# CCP_MCU_IO_CN11.net
KiCad netlist of a schematic drawn in Altium Designer
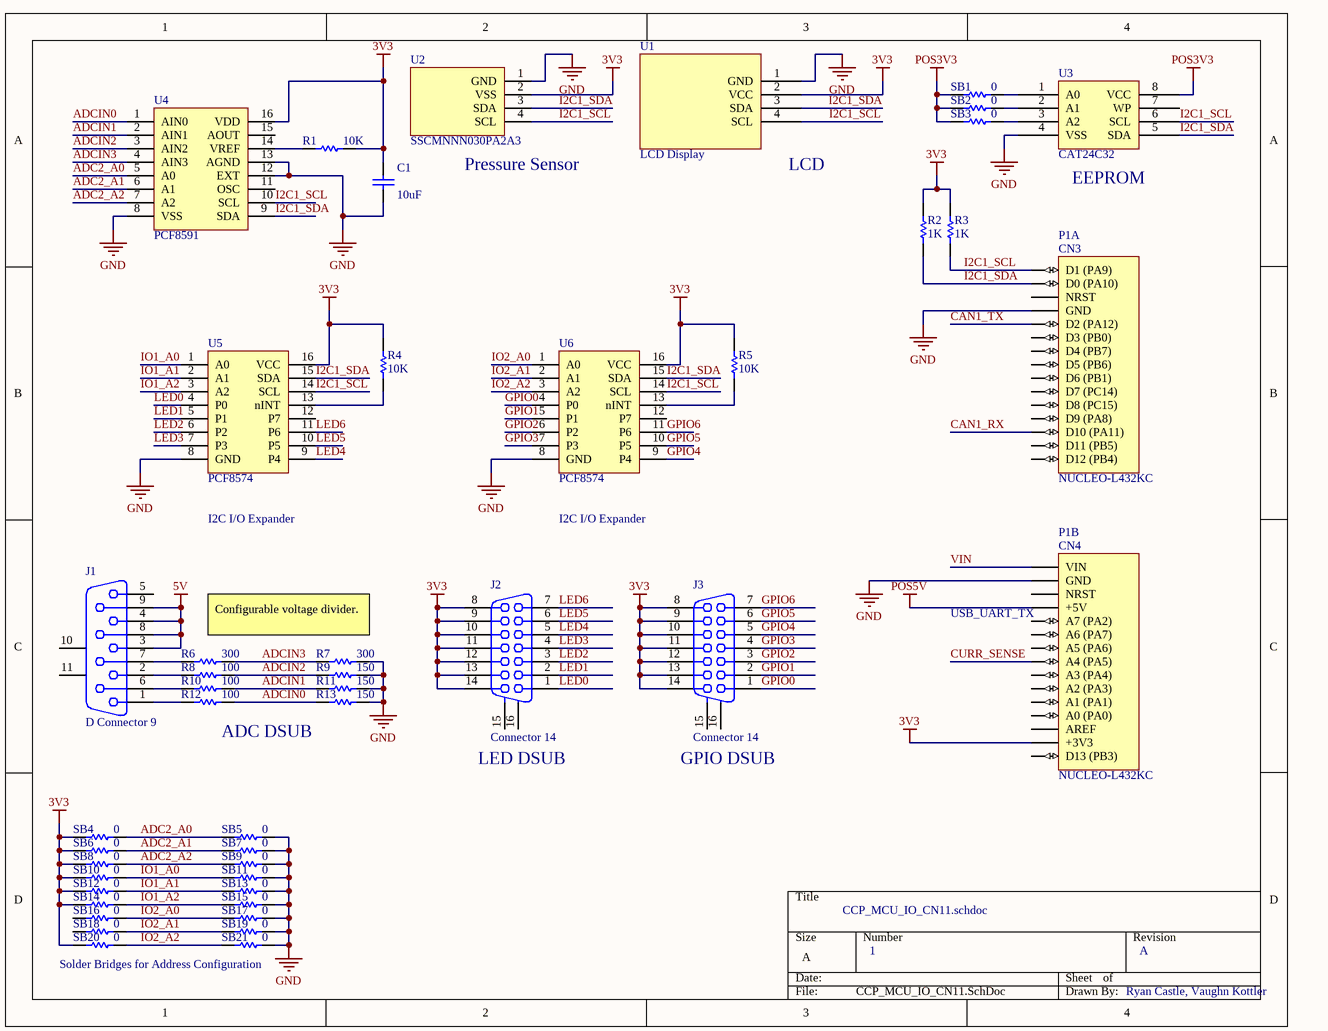
[diagram p0: CCP_MCU_IO_CN11.SchDoc]

(export (version "E")
  (design (tool "Eeschema 10.0.6"))
  (components
    (comp (ref "C1")
      (value "10uF")
      (footprint "C1206")
      (description "Capacitor")
      (fields (field (name "Comment") "Cap") (field (name "PUBLISHER") "Altium Limited"))
      (libsource (lib "Miscellaneous Devices") (part "Cap"))
    )
    (comp (ref "J1")
      (value "D Connector 9")
      (footprint "DSUB1.385-2H9")
      (description "Receptacle Assembly, 9 Position, Right Angle")
      (fields (field (name "PUBLISHER") "Altium Limited"))
      (libsource (lib "Miscellaneous Connectors") (part "D Connector 9"))
    )
    (comp (ref "J2")
      (value "Connector 14")
      (footprint "CHAMP1.27-2H14A")
      (description "Receptacle Header Assemby")
      (fields (field (name "PUBLISHER") "Altium Limited"))
      (libsource (lib "Miscellaneous Connectors") (part "Connector 14"))
    )
    (comp (ref "J3")
      (value "Connector 14")
      (footprint "CHAMP1.27-2H14A")
      (description "Receptacle Header Assemby")
      (fields (field (name "PUBLISHER") "Altium Limited"))
      (libsource (lib "Miscellaneous Connectors") (part "Connector 14"))
    )
    (comp (ref "P1")
      (value "NUCLEO-L432KC")
      (footprint "NUCLEO-32")
      (description "STM32L432KC Development Board")
      (libsource (lib "ic") (part "NUCLEO-L432KC"))
    )
    (comp (ref "R1")
      (value "10K")
      (footprint "6-0805_M")
      (description "Resistor")
      (fields (field (name "Comment") "Res1") (field (name "PUBLISHER") "Altium Limited"))
      (libsource (lib "Miscellaneous Devices") (part "Res1"))
    )
    (comp (ref "R2")
      (value "1K")
      (footprint "6-0805_M")
      (description "Resistor")
      (fields (field (name "Comment") "Res1") (field (name "PUBLISHER") "Altium Limited"))
      (libsource (lib "Miscellaneous Devices") (part "Res1"))
    )
    (comp (ref "R3")
      (value "1K")
      (footprint "6-0805_M")
      (description "Resistor")
      (fields (field (name "Comment") "Res1") (field (name "PUBLISHER") "Altium Limited"))
      (libsource (lib "Miscellaneous Devices") (part "Res1"))
    )
    (comp (ref "R4")
      (value "10K")
      (footprint "6-0805_M")
      (description "Resistor")
      (fields (field (name "Comment") "Res1") (field (name "PUBLISHER") "Altium Limited"))
      (libsource (lib "Miscellaneous Devices") (part "Res1"))
    )
    (comp (ref "R5")
      (value "10K")
      (footprint "6-0805_M")
      (description "Resistor")
      (fields (field (name "Comment") "Res1") (field (name "PUBLISHER") "Altium Limited"))
      (libsource (lib "Miscellaneous Devices") (part "Res1"))
    )
    (comp (ref "R6")
      (value "300")
      (footprint "6-0805_M")
      (description "Resistor")
      (fields (field (name "Comment") "Res1") (field (name "PUBLISHER") "Altium Limited"))
      (libsource (lib "Miscellaneous Devices") (part "Res1"))
    )
    (comp (ref "R7")
      (value "300")
      (footprint "6-0805_M")
      (description "Resistor")
      (fields (field (name "Comment") "Res1") (field (name "PUBLISHER") "Altium Limited"))
      (libsource (lib "Miscellaneous Devices") (part "Res1"))
    )
    (comp (ref "R8")
      (value "100")
      (footprint "6-0805_M")
      (description "Resistor")
      (fields (field (name "Comment") "Res1") (field (name "PUBLISHER") "Altium Limited"))
      (libsource (lib "Miscellaneous Devices") (part "Res1"))
    )
    (comp (ref "R9")
      (value "150")
      (footprint "6-0805_M")
      (description "Resistor")
      (fields (field (name "Comment") "Res1") (field (name "PUBLISHER") "Altium Limited"))
      (libsource (lib "Miscellaneous Devices") (part "Res1"))
    )
    (comp (ref "R10")
      (value "100")
      (footprint "6-0805_M")
      (description "Resistor")
      (fields (field (name "Comment") "Res1") (field (name "PUBLISHER") "Altium Limited"))
      (libsource (lib "Miscellaneous Devices") (part "Res1"))
    )
    (comp (ref "R11")
      (value "150")
      (footprint "6-0805_M")
      (description "Resistor")
      (fields (field (name "Comment") "Res1") (field (name "PUBLISHER") "Altium Limited"))
      (libsource (lib "Miscellaneous Devices") (part "Res1"))
    )
    (comp (ref "R12")
      (value "100")
      (footprint "6-0805_M")
      (description "Resistor")
      (fields (field (name "Comment") "Res1") (field (name "PUBLISHER") "Altium Limited"))
      (libsource (lib "Miscellaneous Devices") (part "Res1"))
    )
    (comp (ref "R13")
      (value "150")
      (footprint "6-0805_M")
      (description "Resistor")
      (fields (field (name "Comment") "Res1") (field (name "PUBLISHER") "Altium Limited"))
      (libsource (lib "Miscellaneous Devices") (part "Res1"))
    )
    (comp (ref "SB1")
      (value "0")
      (footprint "6-0805_M")
      (description "Resistor")
      (fields (field (name "Comment") "Res1") (field (name "PUBLISHER") "Altium Limited"))
      (libsource (lib "Miscellaneous Devices") (part "Res1"))
    )
    (comp (ref "SB2")
      (value "0")
      (footprint "6-0805_M")
      (description "Resistor")
      (fields (field (name "Comment") "Res1") (field (name "PUBLISHER") "Altium Limited"))
      (libsource (lib "Miscellaneous Devices") (part "Res1"))
    )
    (comp (ref "SB3")
      (value "0")
      (footprint "6-0805_M")
      (description "Resistor")
      (fields (field (name "Comment") "Res1") (field (name "PUBLISHER") "Altium Limited"))
      (libsource (lib "Miscellaneous Devices") (part "Res1"))
    )
    (comp (ref "SB4")
      (value "0")
      (footprint "6-0805_M")
      (description "Resistor")
      (fields (field (name "Comment") "Res1") (field (name "PUBLISHER") "Altium Limited"))
      (libsource (lib "Miscellaneous Devices") (part "Res1"))
    )
    (comp (ref "SB5")
      (value "0")
      (footprint "6-0805_M")
      (description "Resistor")
      (fields (field (name "Comment") "Res1") (field (name "PUBLISHER") "Altium Limited"))
      (libsource (lib "Miscellaneous Devices") (part "Res1"))
    )
    (comp (ref "SB6")
      (value "0")
      (footprint "6-0805_M")
      (description "Resistor")
      (fields (field (name "Comment") "Res1") (field (name "PUBLISHER") "Altium Limited"))
      (libsource (lib "Miscellaneous Devices") (part "Res1"))
    )
    (comp (ref "SB7")
      (value "0")
      (footprint "6-0805_M")
      (description "Resistor")
      (fields (field (name "Comment") "Res1") (field (name "PUBLISHER") "Altium Limited"))
      (libsource (lib "Miscellaneous Devices") (part "Res1"))
    )
    (comp (ref "SB8")
      (value "0")
      (footprint "6-0805_M")
      (description "Resistor")
      (fields (field (name "Comment") "Res1") (field (name "PUBLISHER") "Altium Limited"))
      (libsource (lib "Miscellaneous Devices") (part "Res1"))
    )
    (comp (ref "SB9")
      (value "0")
      (footprint "6-0805_M")
      (description "Resistor")
      (fields (field (name "Comment") "Res1") (field (name "PUBLISHER") "Altium Limited"))
      (libsource (lib "Miscellaneous Devices") (part "Res1"))
    )
    (comp (ref "SB10")
      (value "0")
      (footprint "6-0805_M")
      (description "Resistor")
      (fields (field (name "Comment") "Res1") (field (name "PUBLISHER") "Altium Limited"))
      (libsource (lib "Miscellaneous Devices") (part "Res1"))
    )
    (comp (ref "SB11")
      (value "0")
      (footprint "6-0805_M")
      (description "Resistor")
      (fields (field (name "Comment") "Res1") (field (name "PUBLISHER") "Altium Limited"))
      (libsource (lib "Miscellaneous Devices") (part "Res1"))
    )
    (comp (ref "SB12")
      (value "0")
      (footprint "6-0805_M")
      (description "Resistor")
      (fields (field (name "Comment") "Res1") (field (name "PUBLISHER") "Altium Limited"))
      (libsource (lib "Miscellaneous Devices") (part "Res1"))
    )
    (comp (ref "SB13")
      (value "0")
      (footprint "6-0805_M")
      (description "Resistor")
      (fields (field (name "Comment") "Res1") (field (name "PUBLISHER") "Altium Limited"))
      (libsource (lib "Miscellaneous Devices") (part "Res1"))
    )
    (comp (ref "SB14")
      (value "0")
      (footprint "6-0805_M")
      (description "Resistor")
      (fields (field (name "Comment") "Res1") (field (name "PUBLISHER") "Altium Limited"))
      (libsource (lib "Miscellaneous Devices") (part "Res1"))
    )
    (comp (ref "SB15")
      (value "0")
      (footprint "6-0805_M")
      (description "Resistor")
      (fields (field (name "Comment") "Res1") (field (name "PUBLISHER") "Altium Limited"))
      (libsource (lib "Miscellaneous Devices") (part "Res1"))
    )
    (comp (ref "SB16")
      (value "0")
      (footprint "6-0805_M")
      (description "Resistor")
      (fields (field (name "Comment") "Res1") (field (name "PUBLISHER") "Altium Limited"))
      (libsource (lib "Miscellaneous Devices") (part "Res1"))
    )
    (comp (ref "SB17")
      (value "0")
      (footprint "6-0805_M")
      (description "Resistor")
      (fields (field (name "Comment") "Res1") (field (name "PUBLISHER") "Altium Limited"))
      (libsource (lib "Miscellaneous Devices") (part "Res1"))
    )
    (comp (ref "SB18")
      (value "0")
      (footprint "6-0805_M")
      (description "Resistor")
      (fields (field (name "Comment") "Res1") (field (name "PUBLISHER") "Altium Limited"))
      (libsource (lib "Miscellaneous Devices") (part "Res1"))
    )
    (comp (ref "SB19")
      (value "0")
      (footprint "6-0805_M")
      (description "Resistor")
      (fields (field (name "Comment") "Res1") (field (name "PUBLISHER") "Altium Limited"))
      (libsource (lib "Miscellaneous Devices") (part "Res1"))
    )
    (comp (ref "SB20")
      (value "0")
      (footprint "6-0805_M")
      (description "Resistor")
      (fields (field (name "Comment") "Res1") (field (name "PUBLISHER") "Altium Limited"))
      (libsource (lib "Miscellaneous Devices") (part "Res1"))
    )
    (comp (ref "SB21")
      (value "0")
      (footprint "6-0805_M")
      (description "Resistor")
      (fields (field (name "Comment") "Res1") (field (name "PUBLISHER") "Altium Limited"))
      (libsource (lib "Miscellaneous Devices") (part "Res1"))
    )
    (comp (ref "U1")
      (value "LCD Display")
      (footprint "4POS TERM BLOCK")
      (libsource (lib "ic") (part "B01LC8HZ2O"))
    )
    (comp (ref "U2")
      (value "SSCMNNN030PA2A3")
      (footprint "8-SMT")
      (description "Honeywell Digital Pressure Sensor")
      (libsource (lib "ic") (part "SSCMNNN030PA2A3"))
    )
    (comp (ref "U3")
      (value "CAT24C32")
      (footprint "SO8_N")
      (description "I2C EEPROM")
      (libsource (lib "ic") (part "CAT24C32"))
    )
    (comp (ref "U4")
      (value "PCF8591")
      (footprint "16-SOIC")
      (description "8-bit A/D and D/A")
      (libsource (lib "ic") (part "PCF8591"))
    )
    (comp (ref "U5")
      (value "PCF8574")
      (footprint "16-SOIC")
      (description "I2C I/O Expander")
      (libsource (lib "ic") (part "PCF8574"))
    )
    (comp (ref "U6")
      (value "PCF8574")
      (footprint "16-SOIC")
      (description "I2C I/O Expander")
      (libsource (lib "ic") (part "PCF8574"))
    )
  )
  (nets
    (net (code "1") (name "/ADC2_A0") (class "Default")
      (node (ref "SB4") (pin "1") (pinfunction "1_1") (pintype "passive"))
      (node (ref "SB5") (pin "2") (pinfunction "2_2") (pintype "passive"))
      (node (ref "U4") (pin "5") (pinfunction "A0_5") (pintype "passive"))
    )
    (net (code "2") (name "/ADC2_A1") (class "Default")
      (node (ref "SB6") (pin "1") (pinfunction "1_1") (pintype "passive"))
      (node (ref "SB7") (pin "2") (pinfunction "2_2") (pintype "passive"))
      (node (ref "U4") (pin "6") (pinfunction "A1_6") (pintype "passive"))
    )
    (net (code "3") (name "/ADC2_A2") (class "Default")
      (node (ref "SB8") (pin "1") (pinfunction "1_1") (pintype "passive"))
      (node (ref "SB9") (pin "2") (pinfunction "2_2") (pintype "passive"))
      (node (ref "U4") (pin "7") (pinfunction "A2_7") (pintype "passive"))
    )
    (net (code "4") (name "/ADCIN0") (class "Default")
      (node (ref "R12") (pin "1") (pinfunction "1_1") (pintype "passive"))
      (node (ref "R13") (pin "2") (pinfunction "2_2") (pintype "passive"))
      (node (ref "U4") (pin "1") (pinfunction "AIN0_1") (pintype "passive"))
    )
    (net (code "5") (name "/ADCIN1") (class "Default")
      (node (ref "R10") (pin "1") (pinfunction "1_1") (pintype "passive"))
      (node (ref "R11") (pin "2") (pinfunction "2_2") (pintype "passive"))
      (node (ref "U4") (pin "2") (pinfunction "AIN1_2") (pintype "passive"))
    )
    (net (code "6") (name "/ADCIN2") (class "Default")
      (node (ref "R8") (pin "1") (pinfunction "1_1") (pintype "passive"))
      (node (ref "R9") (pin "2") (pinfunction "2_2") (pintype "passive"))
      (node (ref "U4") (pin "3") (pinfunction "AIN2_3") (pintype "passive"))
    )
    (net (code "7") (name "/ADCIN3") (class "Default")
      (node (ref "R6") (pin "1") (pinfunction "1_1") (pintype "passive"))
      (node (ref "R7") (pin "2") (pinfunction "2_2") (pintype "passive"))
      (node (ref "U4") (pin "4") (pinfunction "AIN3_4") (pintype "passive"))
    )
    (net (code "8") (name "/CAN1_RX") (class "Default")
      (node (ref "P1") (pin "13") (pinfunction "D10_(PA11)_13") (pintype "bidirectional"))
    )
    (net (code "9") (name "/CAN1_TX") (class "Default")
      (node (ref "P1") (pin "5") (pinfunction "D2_(PA12)_5") (pintype "bidirectional"))
    )
    (net (code "10") (name "/CURR_SENSE") (class "Default")
      (node (ref "P1") (pin "23") (pinfunction "A4_(PA5)_23") (pintype "bidirectional"))
    )
    (net (code "11") (name "/GPIO0") (class "Default")
      (node (ref "J3") (pin "1") (pinfunction "1_1") (pintype "passive"))
      (node (ref "U6") (pin "4") (pinfunction "P0_4") (pintype "passive"))
    )
    (net (code "12") (name "/GPIO1") (class "Default")
      (node (ref "J3") (pin "2") (pinfunction "2_2") (pintype "passive"))
      (node (ref "U6") (pin "5") (pinfunction "P1_5") (pintype "passive"))
    )
    (net (code "13") (name "/GPIO2") (class "Default")
      (node (ref "J3") (pin "3") (pinfunction "3_3") (pintype "passive"))
      (node (ref "U6") (pin "6") (pinfunction "P2_6") (pintype "passive"))
    )
    (net (code "14") (name "/GPIO3") (class "Default")
      (node (ref "J3") (pin "4") (pinfunction "4_4") (pintype "passive"))
      (node (ref "U6") (pin "7") (pinfunction "P3_7") (pintype "passive"))
    )
    (net (code "15") (name "/GPIO4") (class "Default")
      (node (ref "J3") (pin "5") (pinfunction "5_5") (pintype "passive"))
      (node (ref "U6") (pin "9") (pinfunction "P4_9") (pintype "passive"))
    )
    (net (code "16") (name "/GPIO5") (class "Default")
      (node (ref "J3") (pin "6") (pinfunction "6_6") (pintype "passive"))
      (node (ref "U6") (pin "10") (pinfunction "P5_10") (pintype "passive"))
    )
    (net (code "17") (name "/GPIO6") (class "Default")
      (node (ref "J3") (pin "7") (pinfunction "7_7") (pintype "passive"))
      (node (ref "U6") (pin "11") (pinfunction "P6_11") (pintype "passive"))
    )
    (net (code "18") (name "/I2C1_SCL") (class "Default")
      (node (ref "P1") (pin "1") (pinfunction "D1_(PA9)_1") (pintype "bidirectional"))
      (node (ref "R3") (pin "1") (pinfunction "1_1") (pintype "passive"))
      (node (ref "U1") (pin "4") (pinfunction "SCL_4") (pintype "passive"))
      (node (ref "U2") (pin "4") (pinfunction "SCL_4") (pintype "passive"))
      (node (ref "U3") (pin "6") (pinfunction "SCL_6") (pintype "passive"))
      (node (ref "U4") (pin "10") (pinfunction "SCL_10") (pintype "passive"))
      (node (ref "U5") (pin "14") (pinfunction "SCL_14") (pintype "passive"))
      (node (ref "U6") (pin "14") (pinfunction "SCL_14") (pintype "passive"))
    )
    (net (code "19") (name "/I2C1_SDA") (class "Default")
      (node (ref "P1") (pin "2") (pinfunction "D0_(PA10)_2") (pintype "bidirectional"))
      (node (ref "R2") (pin "1") (pinfunction "1_1") (pintype "passive"))
      (node (ref "U1") (pin "3") (pinfunction "SDA_3") (pintype "passive"))
      (node (ref "U2") (pin "3") (pinfunction "SDA_3") (pintype "passive"))
      (node (ref "U3") (pin "5") (pinfunction "SDA_5") (pintype "passive"))
      (node (ref "U4") (pin "9") (pinfunction "SDA_9") (pintype "passive"))
      (node (ref "U5") (pin "15") (pinfunction "SDA_15") (pintype "passive"))
      (node (ref "U6") (pin "15") (pinfunction "SDA_15") (pintype "passive"))
    )
    (net (code "20") (name "/IO1_A0") (class "Default")
      (node (ref "SB10") (pin "1") (pinfunction "1_1") (pintype "passive"))
      (node (ref "SB11") (pin "2") (pinfunction "2_2") (pintype "passive"))
      (node (ref "U5") (pin "1") (pinfunction "A0_1") (pintype "passive"))
    )
    (net (code "21") (name "/IO1_A1") (class "Default")
      (node (ref "SB12") (pin "1") (pinfunction "1_1") (pintype "passive"))
      (node (ref "SB13") (pin "2") (pinfunction "2_2") (pintype "passive"))
      (node (ref "U5") (pin "2") (pinfunction "A1_2") (pintype "passive"))
    )
    (net (code "22") (name "/IO1_A2") (class "Default")
      (node (ref "SB14") (pin "1") (pinfunction "1_1") (pintype "passive"))
      (node (ref "SB15") (pin "2") (pinfunction "2_2") (pintype "passive"))
      (node (ref "U5") (pin "3") (pinfunction "A2_3") (pintype "passive"))
    )
    (net (code "23") (name "/IO2_A0") (class "Default")
      (node (ref "SB16") (pin "1") (pinfunction "1_1") (pintype "passive"))
      (node (ref "SB17") (pin "2") (pinfunction "2_2") (pintype "passive"))
      (node (ref "U6") (pin "1") (pinfunction "A0_1") (pintype "passive"))
    )
    (net (code "24") (name "/IO2_A1") (class "Default")
      (node (ref "SB18") (pin "1") (pinfunction "1_1") (pintype "passive"))
      (node (ref "SB19") (pin "2") (pinfunction "2_2") (pintype "passive"))
      (node (ref "U6") (pin "2") (pinfunction "A1_2") (pintype "passive"))
    )
    (net (code "25") (name "/IO2_A2") (class "Default")
      (node (ref "SB20") (pin "1") (pinfunction "1_1") (pintype "passive"))
      (node (ref "SB21") (pin "2") (pinfunction "2_2") (pintype "passive"))
      (node (ref "U6") (pin "3") (pinfunction "A2_3") (pintype "passive"))
    )
    (net (code "26") (name "/LED0") (class "Default")
      (node (ref "J2") (pin "1") (pinfunction "1_1") (pintype "passive"))
      (node (ref "U5") (pin "4") (pinfunction "P0_4") (pintype "passive"))
    )
    (net (code "27") (name "/LED1") (class "Default")
      (node (ref "J2") (pin "2") (pinfunction "2_2") (pintype "passive"))
      (node (ref "U5") (pin "5") (pinfunction "P1_5") (pintype "passive"))
    )
    (net (code "28") (name "/LED2") (class "Default")
      (node (ref "J2") (pin "3") (pinfunction "3_3") (pintype "passive"))
      (node (ref "U5") (pin "6") (pinfunction "P2_6") (pintype "passive"))
    )
    (net (code "29") (name "/LED3") (class "Default")
      (node (ref "J2") (pin "4") (pinfunction "4_4") (pintype "passive"))
      (node (ref "U5") (pin "7") (pinfunction "P3_7") (pintype "passive"))
    )
    (net (code "30") (name "/LED4") (class "Default")
      (node (ref "J2") (pin "5") (pinfunction "5_5") (pintype "passive"))
      (node (ref "U5") (pin "9") (pinfunction "P4_9") (pintype "passive"))
    )
    (net (code "31") (name "/LED5") (class "Default")
      (node (ref "J2") (pin "6") (pinfunction "6_6") (pintype "passive"))
      (node (ref "U5") (pin "10") (pinfunction "P5_10") (pintype "passive"))
    )
    (net (code "32") (name "/LED6") (class "Default")
      (node (ref "J2") (pin "7") (pinfunction "7_7") (pintype "passive"))
      (node (ref "U5") (pin "11") (pinfunction "P6_11") (pintype "passive"))
    )
    (net (code "33") (name "/VIN") (class "Default")
      (node (ref "P1") (pin "30") (pinfunction "VIN_30") (pintype "power_in"))
    )
    (net (code "34") (name "3V3") (class "Default")
      (node (ref "C1") (pin "2") (pinfunction "2_2") (pintype "passive"))
      (node (ref "J2") (pin "10") (pinfunction "10_10") (pintype "passive"))
      (node (ref "J2") (pin "11") (pinfunction "11_11") (pintype "passive"))
      (node (ref "J2") (pin "12") (pinfunction "12_12") (pintype "passive"))
      (node (ref "J2") (pin "13") (pinfunction "13_13") (pintype "passive"))
      (node (ref "J2") (pin "14") (pinfunction "14_14") (pintype "passive"))
      (node (ref "J2") (pin "8") (pinfunction "8_8") (pintype "passive"))
      (node (ref "J2") (pin "9") (pinfunction "9_9") (pintype "passive"))
      (node (ref "J3") (pin "10") (pinfunction "10_10") (pintype "passive"))
      (node (ref "J3") (pin "11") (pinfunction "11_11") (pintype "passive"))
      (node (ref "J3") (pin "12") (pinfunction "12_12") (pintype "passive"))
      (node (ref "J3") (pin "13") (pinfunction "13_13") (pintype "passive"))
      (node (ref "J3") (pin "14") (pinfunction "14_14") (pintype "passive"))
      (node (ref "J3") (pin "8") (pinfunction "8_8") (pintype "passive"))
      (node (ref "J3") (pin "9") (pinfunction "9_9") (pintype "passive"))
      (node (ref "P1") (pin "17") (pinfunction "+3V3_17") (pintype "power_in"))
      (node (ref "R1") (pin "1") (pinfunction "1_1") (pintype "passive"))
      (node (ref "R2") (pin "2") (pinfunction "2_2") (pintype "passive"))
      (node (ref "R3") (pin "2") (pinfunction "2_2") (pintype "passive"))
      (node (ref "R4") (pin "2") (pinfunction "2_2") (pintype "passive"))
      (node (ref "R5") (pin "2") (pinfunction "2_2") (pintype "passive"))
      (node (ref "SB10") (pin "2") (pinfunction "2_2") (pintype "passive"))
      (node (ref "SB12") (pin "2") (pinfunction "2_2") (pintype "passive"))
      (node (ref "SB14") (pin "2") (pinfunction "2_2") (pintype "passive"))
      (node (ref "SB20") (pin "2") (pinfunction "2_2") (pintype "passive"))
      (node (ref "SB4") (pin "2") (pinfunction "2_2") (pintype "passive"))
      (node (ref "SB6") (pin "2") (pinfunction "2_2") (pintype "passive"))
      (node (ref "SB8") (pin "2") (pinfunction "2_2") (pintype "passive"))
      (node (ref "U1") (pin "2") (pinfunction "VCC_2") (pintype "passive"))
      (node (ref "U2") (pin "2") (pinfunction "VSS_2") (pintype "power_in"))
      (node (ref "U4") (pin "16") (pinfunction "VDD_16") (pintype "passive"))
      (node (ref "U5") (pin "16") (pinfunction "VCC_16") (pintype "passive"))
      (node (ref "U6") (pin "16") (pinfunction "VCC_16") (pintype "passive"))
    )
    (net (code "35") (name "5V") (class "Default")
      (node (ref "J1") (pin "3") (pinfunction "3_3") (pintype "passive"))
      (node (ref "J1") (pin "4") (pinfunction "4_4") (pintype "passive"))
      (node (ref "J1") (pin "8") (pinfunction "8_8") (pintype "passive"))
      (node (ref "J1") (pin "9") (pinfunction "9_9") (pintype "passive"))
    )
    (net (code "36") (name "GND") (class "Default")
      (node (ref "C1") (pin "1") (pinfunction "1_1") (pintype "passive"))
      (node (ref "P1") (pin "29") (pinfunction "GND_29") (pintype "power_in"))
      (node (ref "P1") (pin "4") (pinfunction "GND_4") (pintype "power_in"))
      (node (ref "R11") (pin "1") (pinfunction "1_1") (pintype "passive"))
      (node (ref "R13") (pin "1") (pinfunction "1_1") (pintype "passive"))
      (node (ref "R7") (pin "1") (pinfunction "1_1") (pintype "passive"))
      (node (ref "R9") (pin "1") (pinfunction "1_1") (pintype "passive"))
      (node (ref "SB11") (pin "1") (pinfunction "1_1") (pintype "passive"))
      (node (ref "SB13") (pin "1") (pinfunction "1_1") (pintype "passive"))
      (node (ref "SB15") (pin "1") (pinfunction "1_1") (pintype "passive"))
      (node (ref "SB17") (pin "1") (pinfunction "1_1") (pintype "passive"))
      (node (ref "SB19") (pin "1") (pinfunction "1_1") (pintype "passive"))
      (node (ref "SB21") (pin "1") (pinfunction "1_1") (pintype "passive"))
      (node (ref "SB5") (pin "1") (pinfunction "1_1") (pintype "passive"))
      (node (ref "SB7") (pin "1") (pinfunction "1_1") (pintype "passive"))
      (node (ref "SB9") (pin "1") (pinfunction "1_1") (pintype "passive"))
      (node (ref "U1") (pin "1") (pinfunction "GND_1") (pintype "passive"))
      (node (ref "U2") (pin "1") (pinfunction "GND_1") (pintype "passive"))
      (node (ref "U3") (pin "4") (pinfunction "VSS_4") (pintype "passive"))
      (node (ref "U4") (pin "12") (pinfunction "EXT_12") (pintype "passive"))
      (node (ref "U4") (pin "13") (pinfunction "AGND_13") (pintype "passive"))
      (node (ref "U4") (pin "8") (pinfunction "VSS_8") (pintype "passive"))
      (node (ref "U5") (pin "8") (pinfunction "GND_8") (pintype "passive"))
      (node (ref "U6") (pin "8") (pinfunction "GND_8") (pintype "passive"))
    )
    (net (code "37") (name "Net-(J1-Pad1)") (class "Default")
      (node (ref "J1") (pin "1") (pinfunction "1_1") (pintype "passive"))
      (node (ref "R12") (pin "2") (pinfunction "2_2") (pintype "passive"))
    )
    (net (code "38") (name "Net-(J1-Pad2)") (class "Default")
      (node (ref "J1") (pin "2") (pinfunction "2_2") (pintype "passive"))
      (node (ref "R8") (pin "2") (pinfunction "2_2") (pintype "passive"))
    )
    (net (code "39") (name "Net-(J1-Pad6)") (class "Default")
      (node (ref "J1") (pin "6") (pinfunction "6_6") (pintype "passive"))
      (node (ref "R10") (pin "2") (pinfunction "2_2") (pintype "passive"))
    )
    (net (code "40") (name "Net-(J1-Pad7)") (class "Default")
      (node (ref "J1") (pin "7") (pinfunction "7_7") (pintype "passive"))
      (node (ref "R6") (pin "2") (pinfunction "2_2") (pintype "passive"))
    )
    (net (code "41") (name "Net-(U3-A0)") (class "Default")
      (node (ref "SB1") (pin "1") (pinfunction "1_1") (pintype "passive"))
      (node (ref "U3") (pin "1") (pinfunction "A0_1") (pintype "passive"))
    )
    (net (code "42") (name "Net-(U3-A1)") (class "Default")
      (node (ref "SB2") (pin "1") (pinfunction "1_1") (pintype "passive"))
      (node (ref "U3") (pin "2") (pinfunction "A1_2") (pintype "passive"))
    )
    (net (code "43") (name "Net-(U3-A2)") (class "Default")
      (node (ref "SB3") (pin "1") (pinfunction "1_1") (pintype "passive"))
      (node (ref "U3") (pin "3") (pinfunction "A2_3") (pintype "passive"))
    )
    (net (code "44") (name "Net-(U4-VREF)") (class "Default")
      (node (ref "R1") (pin "2") (pinfunction "2_2") (pintype "passive"))
      (node (ref "U4") (pin "14") (pinfunction "VREF_14") (pintype "passive"))
    )
    (net (code "45") (name "Net-(U5-nINT)") (class "Default")
      (node (ref "R4") (pin "1") (pinfunction "1_1") (pintype "passive"))
      (node (ref "U5") (pin "13") (pinfunction "nINT_13") (pintype "passive"))
    )
    (net (code "46") (name "Net-(U6-nINT)") (class "Default")
      (node (ref "R5") (pin "1") (pinfunction "1_1") (pintype "passive"))
      (node (ref "U6") (pin "13") (pinfunction "nINT_13") (pintype "passive"))
    )
    (net (code "47") (name "POS3V3") (class "Default")
      (node (ref "SB1") (pin "2") (pinfunction "2_2") (pintype "passive"))
      (node (ref "SB2") (pin "2") (pinfunction "2_2") (pintype "passive"))
      (node (ref "SB3") (pin "2") (pinfunction "2_2") (pintype "passive"))
      (node (ref "U3") (pin "8") (pinfunction "VCC_8") (pintype "power_in"))
    )
    (net (code "48") (name "POS5V") (class "Default")
      (node (ref "P1") (pin "27") (pinfunction "+5V_27") (pintype "power_in"))
    )
    (net (code "49") (name "unconnected-(J1-MH1-Pad10)") (class "Default")
      (node (ref "J1") (pin "10") (pinfunction "MH1_10") (pintype "passive"))
    )
    (net (code "50") (name "unconnected-(J1-MH2-Pad11)") (class "Default")
      (node (ref "J1") (pin "11") (pinfunction "MH2_11") (pintype "passive"))
    )
    (net (code "51") (name "unconnected-(J1-Pad5)") (class "Default")
      (node (ref "J1") (pin "5") (pinfunction "5_5") (pintype "passive"))
    )
    (net (code "52") (name "unconnected-(J2-MH1-Pad15)") (class "Default")
      (node (ref "J2") (pin "15") (pinfunction "MH1_15") (pintype "passive"))
    )
    (net (code "53") (name "unconnected-(J2-MH2-Pad16)") (class "Default")
      (node (ref "J2") (pin "16") (pinfunction "MH2_16") (pintype "passive"))
    )
    (net (code "54") (name "unconnected-(J3-MH1-Pad15)") (class "Default")
      (node (ref "J3") (pin "15") (pinfunction "MH1_15") (pintype "passive"))
    )
    (net (code "55") (name "unconnected-(J3-MH2-Pad16)") (class "Default")
      (node (ref "J3") (pin "16") (pinfunction "MH2_16") (pintype "passive"))
    )
    (net (code "56") (name "unconnected-(P1A-D3_(PB0)-Pad6)") (class "Default")
      (node (ref "P1") (pin "6") (pinfunction "D3_(PB0)_6") (pintype "bidirectional"))
    )
    (net (code "57") (name "unconnected-(P1A-D4_(PB7)-Pad7)") (class "Default")
      (node (ref "P1") (pin "7") (pinfunction "D4_(PB7)_7") (pintype "bidirectional"))
    )
    (net (code "58") (name "unconnected-(P1A-D5_(PB6)-Pad8)") (class "Default")
      (node (ref "P1") (pin "8") (pinfunction "D5_(PB6)_8") (pintype "bidirectional"))
    )
    (net (code "59") (name "unconnected-(P1A-D6_(PB1)-Pad9)") (class "Default")
      (node (ref "P1") (pin "9") (pinfunction "D6_(PB1)_9") (pintype "bidirectional"))
    )
    (net (code "60") (name "unconnected-(P1A-D7_(PC14)-Pad10)") (class "Default")
      (node (ref "P1") (pin "10") (pinfunction "D7_(PC14)_10") (pintype "bidirectional"))
    )
    (net (code "61") (name "unconnected-(P1A-D8_(PC15)-Pad11)") (class "Default")
      (node (ref "P1") (pin "11") (pinfunction "D8_(PC15)_11") (pintype "bidirectional"))
    )
    (net (code "62") (name "unconnected-(P1A-D9_(PA8)-Pad12)") (class "Default")
      (node (ref "P1") (pin "12") (pinfunction "D9_(PA8)_12") (pintype "bidirectional"))
    )
    (net (code "63") (name "unconnected-(P1A-D11_(PB5)-Pad14)") (class "Default")
      (node (ref "P1") (pin "14") (pinfunction "D11_(PB5)_14") (pintype "bidirectional"))
    )
    (net (code "64") (name "unconnected-(P1A-D12_(PB4)-Pad15)") (class "Default")
      (node (ref "P1") (pin "15") (pinfunction "D12_(PB4)_15") (pintype "bidirectional"))
    )
    (net (code "65") (name "unconnected-(P1A-NRST-Pad3)") (class "Default")
      (node (ref "P1") (pin "3") (pinfunction "NRST_3") (pintype "passive"))
    )
    (net (code "66") (name "unconnected-(P1B-A0_(PA0)-Pad19)") (class "Default")
      (node (ref "P1") (pin "19") (pinfunction "A0_(PA0)_19") (pintype "bidirectional"))
    )
    (net (code "67") (name "unconnected-(P1B-A1_(PA1)-Pad20)") (class "Default")
      (node (ref "P1") (pin "20") (pinfunction "A1_(PA1)_20") (pintype "bidirectional"))
    )
    (net (code "68") (name "unconnected-(P1B-A2_(PA3)-Pad21)") (class "Default")
      (node (ref "P1") (pin "21") (pinfunction "A2_(PA3)_21") (pintype "bidirectional"))
    )
    (net (code "69") (name "unconnected-(P1B-A3_(PA4)-Pad22)") (class "Default")
      (node (ref "P1") (pin "22") (pinfunction "A3_(PA4)_22") (pintype "bidirectional"))
    )
    (net (code "70") (name "unconnected-(P1B-A5_(PA6)-Pad24)") (class "Default")
      (node (ref "P1") (pin "24") (pinfunction "A5_(PA6)_24") (pintype "bidirectional"))
    )
    (net (code "71") (name "unconnected-(P1B-A6_(PA7)-Pad25)") (class "Default")
      (node (ref "P1") (pin "25") (pinfunction "A6_(PA7)_25") (pintype "bidirectional"))
    )
    (net (code "72") (name "unconnected-(P1B-A7_(PA2)-Pad26)") (class "Default")
      (node (ref "P1") (pin "26") (pinfunction "A7_(PA2)_26") (pintype "bidirectional"))
    )
    (net (code "73") (name "unconnected-(P1B-AREF-Pad18)") (class "Default")
      (node (ref "P1") (pin "18") (pinfunction "AREF_18") (pintype "passive"))
    )
    (net (code "74") (name "unconnected-(P1B-D13_(PB3)-Pad16)") (class "Default")
      (node (ref "P1") (pin "16") (pinfunction "D13_(PB3)_16") (pintype "bidirectional"))
    )
    (net (code "75") (name "unconnected-(P1B-NRST-Pad28)") (class "Default")
      (node (ref "P1") (pin "28") (pinfunction "NRST_28") (pintype "passive"))
    )
    (net (code "76") (name "unconnected-(SB16-Pad2)") (class "Default")
      (node (ref "SB16") (pin "2") (pinfunction "2_2") (pintype "passive"))
    )
    (net (code "77") (name "unconnected-(SB18-Pad2)") (class "Default")
      (node (ref "SB18") (pin "2") (pinfunction "2_2") (pintype "passive"))
    )
    (net (code "78") (name "unconnected-(U3-WP-Pad7)") (class "Default")
      (node (ref "U3") (pin "7") (pinfunction "WP_7") (pintype "passive"))
    )
    (net (code "79") (name "unconnected-(U4-AOUT-Pad15)") (class "Default")
      (node (ref "U4") (pin "15") (pinfunction "AOUT_15") (pintype "passive"))
    )
    (net (code "80") (name "unconnected-(U4-OSC-Pad11)") (class "Default")
      (node (ref "U4") (pin "11") (pinfunction "OSC_11") (pintype "passive"))
    )
    (net (code "81") (name "unconnected-(U5-P7-Pad12)") (class "Default")
      (node (ref "U5") (pin "12") (pinfunction "P7_12") (pintype "passive"))
    )
    (net (code "82") (name "unconnected-(U6-P7-Pad12)") (class "Default")
      (node (ref "U6") (pin "12") (pinfunction "P7_12") (pintype "passive"))
    )
  )
)
